# ESP32.net
KiCad netlist of a schematic drawn in Altium Designer
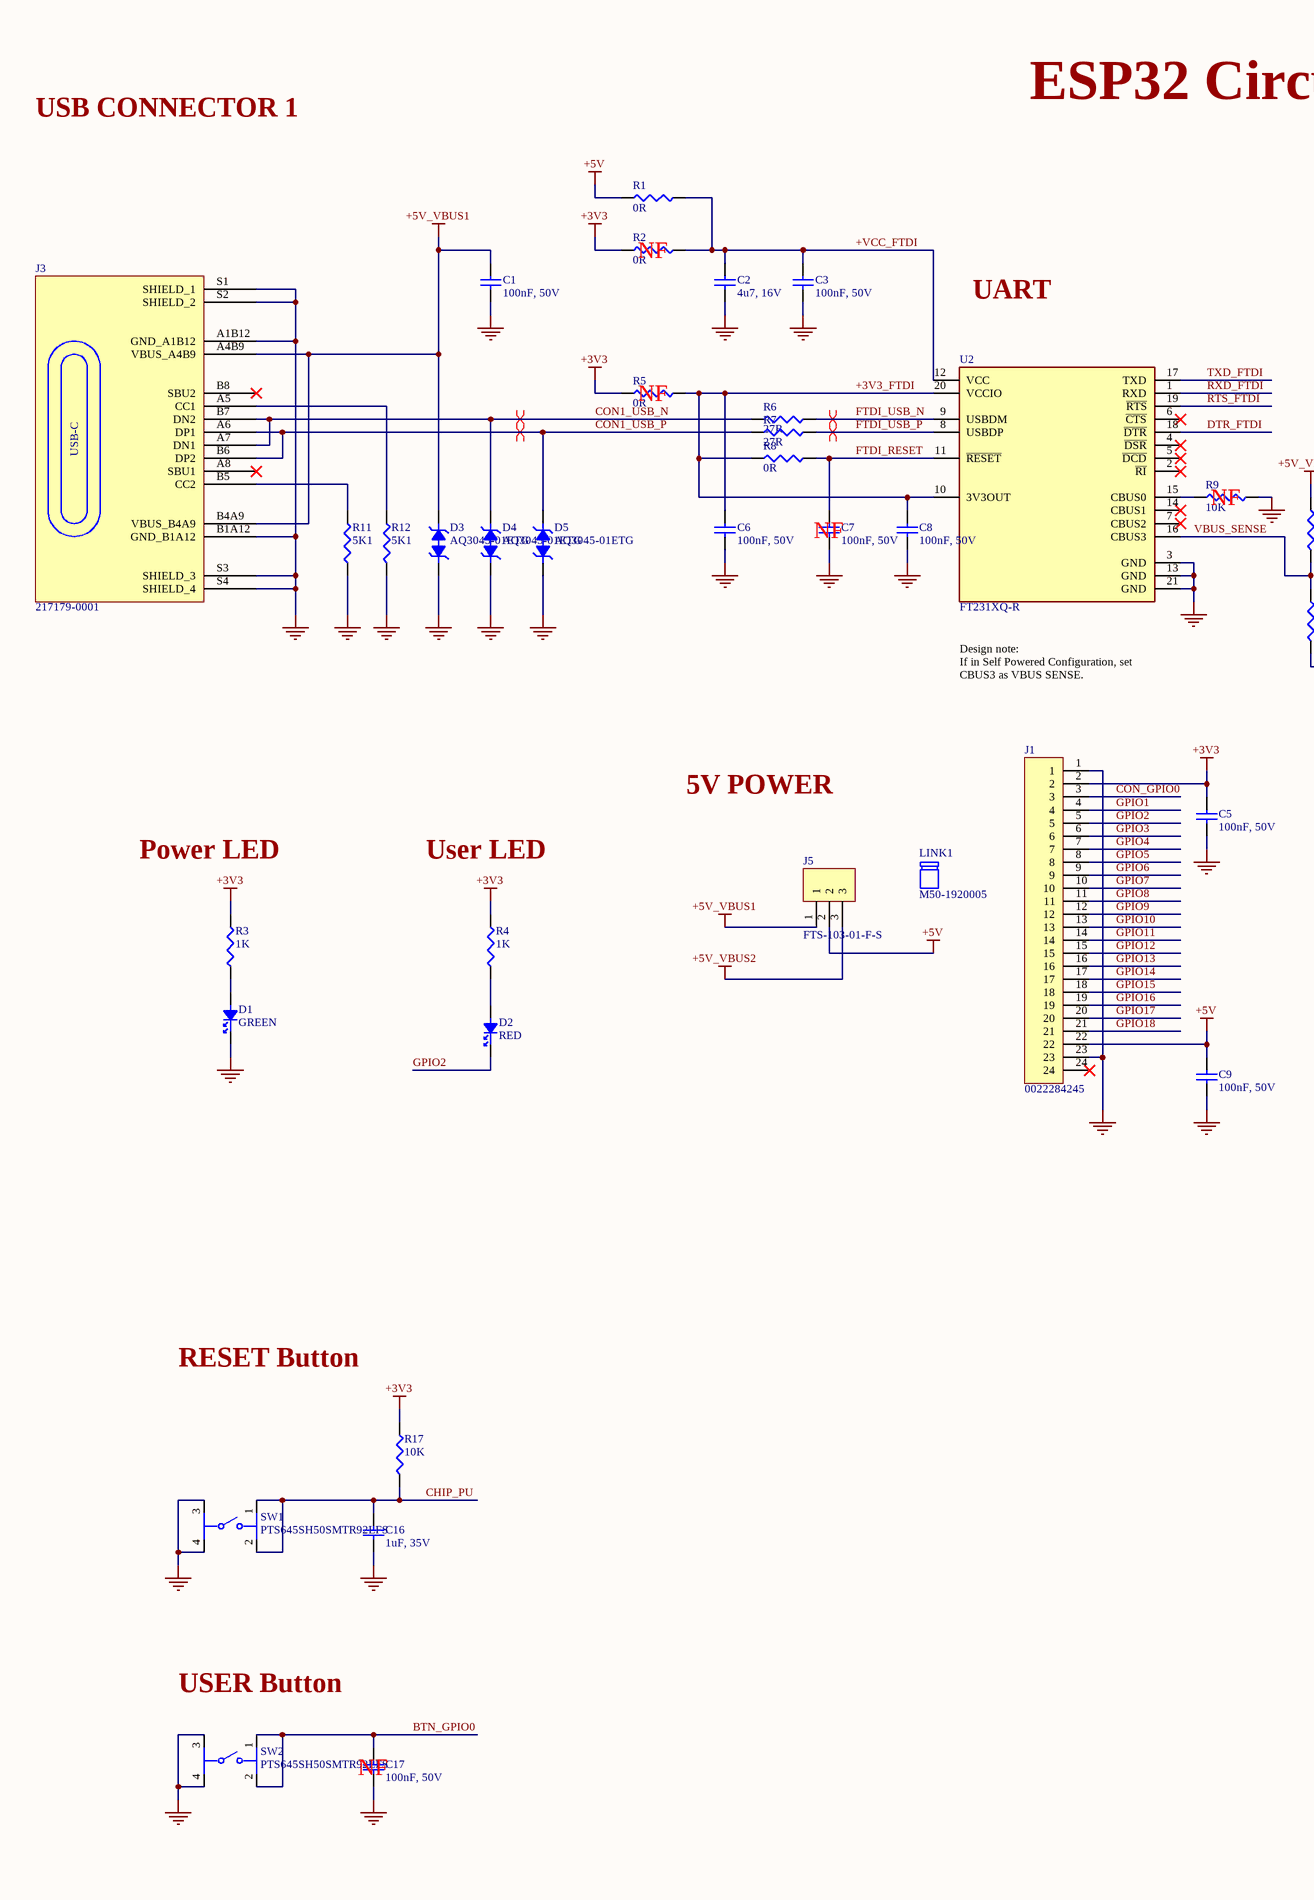
[diagram p0: ESP32 .SchDoc, left]
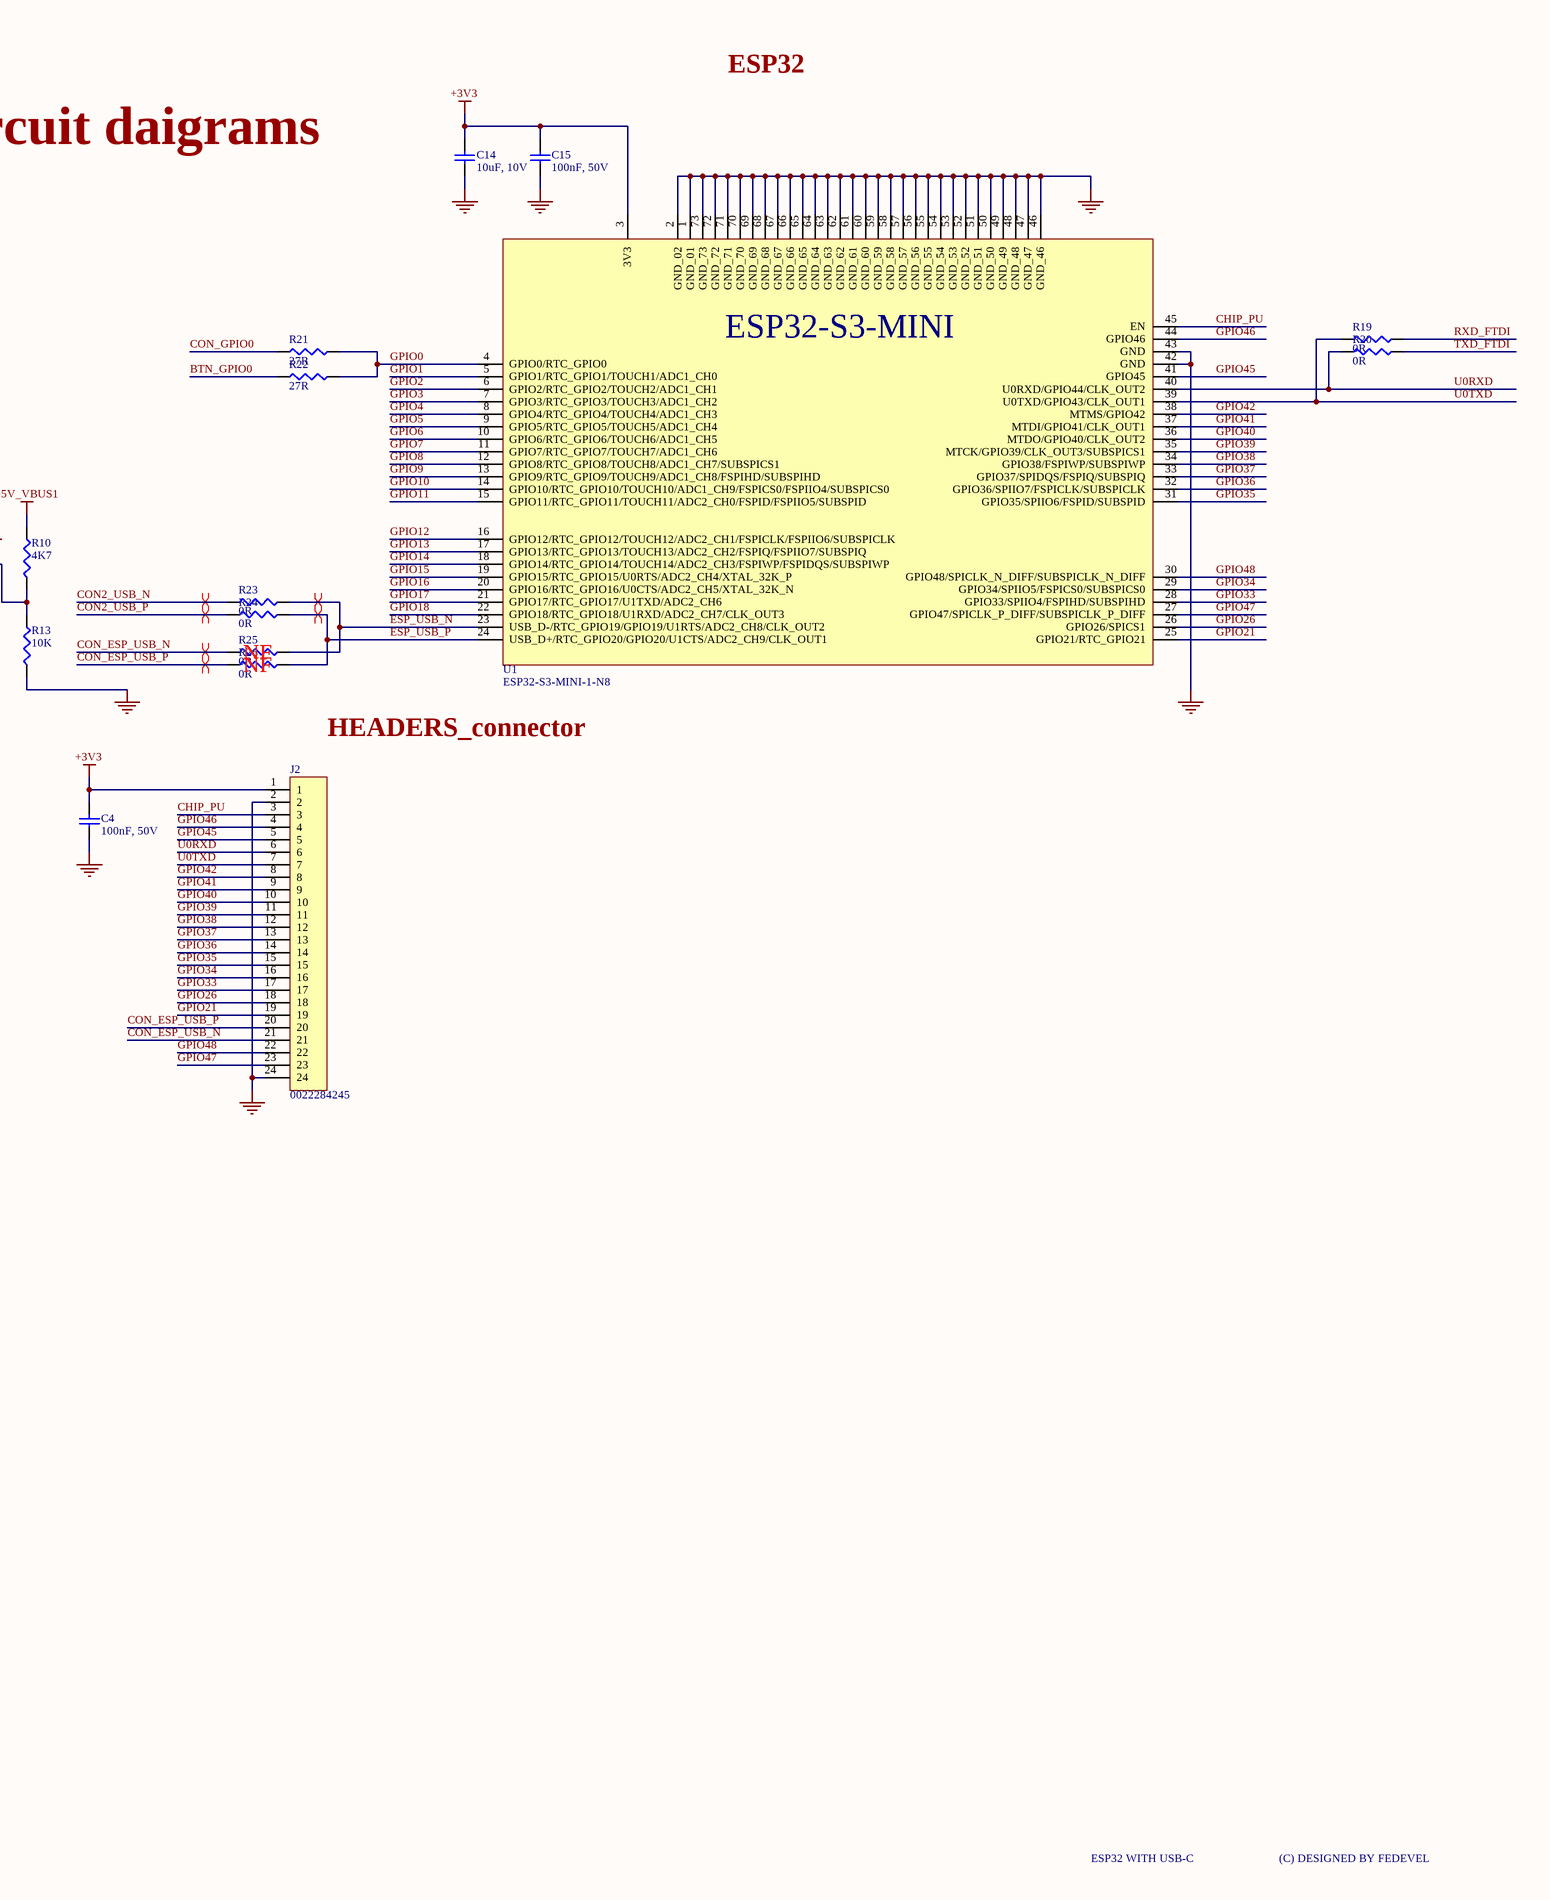
[diagram p1: ESP32 .SchDoc, right]

(export (version "E")
  (design (tool "Eeschema 10.0.6"))
  (components
    (comp (ref "C1")
      (value "100nF, 50V")
      (footprint "CAPC1005X55N")
      (description "CAP CER 0.1UF 50V X7R 0402")
      (fields
        (field (name "MANUFACTURER") "Samsung")
        (field (name "MANUFACTURER PART NUMBER") "CL05B104KB54PNC")
      )
      (libsource (lib "Schlib") (part "CL05B104KB54PNC"))
    )
    (comp (ref "C2")
      (value "4u7, 16V")
      (footprint "CAPC1005X55N")
      (description "CAP CER 4.7UF 16V X5R 0402")
      (fields
        (field (name "MANUFACTURER") "Samsung")
        (field (name "MANUFACTURER PART NUMBER") "CL05A475MO5NUNC")
      )
      (libsource (lib "Schlib") (part "CL05A475MO5NUNC"))
    )
    (comp (ref "C3")
      (value "100nF, 50V")
      (footprint "CAPC1005X55N")
      (description "CAP CER 0.1UF 50V X7R 0402")
      (fields
        (field (name "MANUFACTURER") "Samsung")
        (field (name "MANUFACTURER PART NUMBER") "CL05B104KB54PNC")
      )
      (libsource (lib "Schlib") (part "CL05B104KB54PNC"))
    )
    (comp (ref "C4")
      (value "100nF, 50V")
      (footprint "CAPC1005X55N")
      (description "CAP CER 0.1UF 50V X7R 0402")
      (fields
        (field (name "MANUFACTURER") "Samsung")
        (field (name "MANUFACTURER PART NUMBER") "CL05B104KB54PNC")
      )
      (libsource (lib "Schlib") (part "CL05B104KB54PNC"))
    )
    (comp (ref "C5")
      (value "100nF, 50V")
      (footprint "CAPC1005X55N")
      (description "CAP CER 0.1UF 50V X7R 0402")
      (fields
        (field (name "MANUFACTURER") "Samsung")
        (field (name "MANUFACTURER PART NUMBER") "CL05B104KB54PNC")
      )
      (libsource (lib "Schlib") (part "CL05B104KB54PNC"))
    )
    (comp (ref "C6")
      (value "100nF, 50V")
      (footprint "CAPC1005X55N")
      (description "CAP CER 0.1UF 50V X7R 0402")
      (fields
        (field (name "MANUFACTURER") "Samsung")
        (field (name "MANUFACTURER PART NUMBER") "CL05B104KB54PNC")
      )
      (libsource (lib "Schlib") (part "CL05B104KB54PNC"))
    )
    (comp (ref "C7")
      (value "100nF, 50V")
      (footprint "CAPC1005X55N")
      (description "CAP CER 0.1UF 50V X7R 0402")
      (fields
        (field (name "MANUFACTURER") "Samsung")
        (field (name "MANUFACTURER PART NUMBER") "CL05B104KB54PNC")
      )
      (libsource (lib "Schlib") (part "CL05B104KB54PNC"))
    )
    (comp (ref "C8")
      (value "100nF, 50V")
      (footprint "CAPC1005X55N")
      (description "CAP CER 0.1UF 50V X7R 0402")
      (fields
        (field (name "MANUFACTURER") "Samsung")
        (field (name "MANUFACTURER PART NUMBER") "CL05B104KB54PNC")
      )
      (libsource (lib "Schlib") (part "CL05B104KB54PNC"))
    )
    (comp (ref "C9")
      (value "100nF, 50V")
      (footprint "CAPC1005X55N")
      (description "CAP CER 0.1UF 50V X7R 0402")
      (fields
        (field (name "MANUFACTURER") "Samsung")
        (field (name "MANUFACTURER PART NUMBER") "CL05B104KB54PNC")
      )
      (libsource (lib "Schlib") (part "CL05B104KB54PNC"))
    )
    (comp (ref "C14")
      (value "10uF, 10V")
      (footprint "CAPC1005X55N")
      (description "CAP CER 10UF 10V X5R 0402")
      (fields
        (field (name "MANUFACTURER") "Samsung")
        (field (name "MANUFACTURER PART NUMBER") "CL05A106MP8NUB8")
      )
      (libsource (lib "Schlib") (part "CL05A106MP8NUB8"))
    )
    (comp (ref "C15")
      (value "100nF, 50V")
      (footprint "CAPC1005X55N")
      (description "CAP CER 0.1UF 50V X7R 0402")
      (fields
        (field (name "MANUFACTURER") "Samsung")
        (field (name "MANUFACTURER PART NUMBER") "CL05B104KB54PNC")
      )
      (libsource (lib "Schlib") (part "CL05B104KB54PNC"))
    )
    (comp (ref "C16")
      (value "1uF, 35V")
      (footprint "CAPC1005X55N")
      (description "CAP CER 1UF 35V X5R 0402")
      (fields
        (field (name "MANUFACTURER") "Samsung")
        (field (name "MANUFACTURER PART NUMBER") "CL05A105KL5NRNC")
      )
      (libsource (lib "Schlib") (part "CL05A105KL5NRNC"))
    )
    (comp (ref "C17")
      (value "100nF, 50V")
      (footprint "CAPC1005X55N")
      (description "CAP CER 0.1UF 50V X7R 0402")
      (fields
        (field (name "MANUFACTURER") "Samsung")
        (field (name "MANUFACTURER PART NUMBER") "CL05B104KB54PNC")
      )
      (libsource (lib "Schlib") (part "CL05B104KB54PNC"))
    )
    (comp (ref "D1")
      (value "GREEN")
      (footprint "LED0402G")
      (description "LED YLW-GRN 0402 SMD")
      (fields
        (field (name "MANUFACTURER") "Vishay")
        (field (name "MANUFACTURER PART NUMBER") "VLMG1500-GS08")
      )
      (libsource (lib "Schlib") (part "VLMG1500-GS08"))
    )
    (comp (ref "D2")
      (value "RED")
      (footprint "LED0402R")
      (description "LED RED 0402 SMD")
      (fields
        (field (name "MANUFACTURER") "Vishay")
        (field (name "MANUFACTURER PART NUMBER") "VLMS1500-GS08")
      )
      (libsource (lib "Schlib") (part "VLMS1500-GS08"))
    )
    (comp (ref "D3")
      (value "AQ3045-01ETG")
      (footprint "SOD882")
      (description "TVS DIODE 5.3VWM 12VC SOD882")
      (fields (field (name "MANUFACTURER") "Littelfuse") (field (name "LCSC PART NUMBER") "C3710326"))
      (libsource (lib "Schlib") (part "AQ3045-01ETG"))
    )
    (comp (ref "D4")
      (value "AQ3045-01ETG")
      (footprint "SOD882")
      (description "TVS DIODE 5.3VWM 12VC SOD882")
      (fields (field (name "MANUFACTURER") "Littelfuse") (field (name "LCSC PART NUMBER") "C3710326"))
      (libsource (lib "Schlib") (part "AQ3045-01ETG"))
    )
    (comp (ref "D5")
      (value "AQ3045-01ETG")
      (footprint "SOD882")
      (description "TVS DIODE 5.3VWM 12VC SOD882")
      (fields (field (name "MANUFACTURER") "Littelfuse") (field (name "LCSC PART NUMBER") "C3710326"))
      (libsource (lib "Schlib") (part "AQ3045-01ETG"))
    )
    (comp (ref "J1")
      (value "0022284245")
      (footprint "HDR_1X24_2.54MM")
      (description "CONN HEADER VERT 24POS 2.54MM")
      (fields (field (name "MANUFACTURER") "Molex") (field (name "LCSC PART NUMBER") "C7145888"))
      (libsource (lib "Schlib") (part "0022284245"))
    )
    (comp (ref "J2")
      (value "0022284245")
      (footprint "HDR_1X24_2.54MM")
      (description "CONN HEADER VERT 24POS 2.54MM")
      (fields (field (name "MANUFACTURER") "Molex") (field (name "LCSC PART NUMBER") "C7145888"))
      (libsource (lib "") (part "0022284245_1"))
    )
    (comp (ref "J3")
      (value "217179-0001")
      (footprint "FP-2171790001-MFG")
      (description "CONN RCP USB2.0 TYP C 24P SMD RA")
      (fields (field (name "MANUFACTURER") "Molex") (field (name "LCSC PART NUMBER") "C3197684"))
      (libsource (lib "Schlib") (part "217179-0001"))
    )
    (comp (ref "J5")
      (value "FTS-103-01-F-S")
      (footprint "HDR_1X3_1.27MM")
      (description "CONN HEADER VERT 3POS 1.27MM")
      (fields (field (name "MANUFACTURER") "Samtec") (field (name "LCSC PART NUMBER") "C3333578"))
      (libsource (lib "Schlib") (part "FTS-103-01-F-S"))
    )
    (comp (ref "LINK1")
      (value "M50-1920005")
      (description "CONN SHUNT 1.27MM RED")
      (fields (field (name "MANUFACTURER") "Harwin") (field (name "LCSC PART NUMBER") "C6985646"))
      (libsource (lib "Schlib") (part "M50-1920005"))
    )
    (comp (ref "R1")
      (value "0R")
      (footprint "RESC1005X37N")
      (description "RES 0 OHM JUMPER 1/16W 0402")
      (fields
        (field (name "MANUFACTURER") "Yageo")
        (field (name "MANUFACTURER PART NUMBER") "RC0402JR-070RL")
      )
      (libsource (lib "Schlib") (part "RC0402JR-070RL"))
    )
    (comp (ref "R2")
      (value "0R")
      (footprint "RESC1005X37N")
      (description "RES 0 OHM JUMPER 1/16W 0402")
      (fields
        (field (name "MANUFACTURER") "Yageo")
        (field (name "MANUFACTURER PART NUMBER") "RC0402JR-070RL")
      )
      (libsource (lib "Schlib") (part "RC0402JR-070RL"))
    )
    (comp (ref "R3")
      (value "1K")
      (footprint "RESC1005X37N")
      (description "RES 1K OHM 1% 1/16W 0402")
      (fields
        (field (name "MANUFACTURER") "Yageo")
        (field (name "MANUFACTURER PART NUMBER") "RC0402FR-071KL")
      )
      (libsource (lib "Schlib") (part "RC0402FR-071KL"))
    )
    (comp (ref "R4")
      (value "1K")
      (footprint "RESC1005X37N")
      (description "RES 1K OHM 1% 1/16W 0402")
      (fields
        (field (name "MANUFACTURER") "Yageo")
        (field (name "MANUFACTURER PART NUMBER") "RC0402FR-071KL")
      )
      (libsource (lib "Schlib") (part "RC0402FR-071KL"))
    )
    (comp (ref "R5")
      (value "0R")
      (footprint "RESC1005X37N")
      (description "RES 0 OHM JUMPER 1/16W 0402")
      (fields
        (field (name "MANUFACTURER") "Yageo")
        (field (name "MANUFACTURER PART NUMBER") "RC0402JR-070RL")
      )
      (libsource (lib "Schlib") (part "RC0402JR-070RL"))
    )
    (comp (ref "R6")
      (value "27R")
      (footprint "RESC1005X37N")
      (description "RES 27 OHM 1% 1/16W 0402")
      (fields
        (field (name "MANUFACTURER") "Yageo")
        (field (name "MANUFACTURER PART NUMBER") "RC0402FR-0727RL")
      )
      (libsource (lib "Schlib") (part "RC0402FR-0727RL"))
    )
    (comp (ref "R7")
      (value "27R")
      (footprint "RESC1005X37N")
      (description "RES 27 OHM 1% 1/16W 0402")
      (fields
        (field (name "MANUFACTURER") "Yageo")
        (field (name "MANUFACTURER PART NUMBER") "RC0402FR-0727RL")
      )
      (libsource (lib "Schlib") (part "RC0402FR-0727RL"))
    )
    (comp (ref "R8")
      (value "0R")
      (footprint "RESC1005X37N")
      (description "RES 0 OHM JUMPER 1/16W 0402")
      (fields
        (field (name "MANUFACTURER") "Yageo")
        (field (name "MANUFACTURER PART NUMBER") "RC0402JR-070RL")
      )
      (libsource (lib "Schlib") (part "RC0402JR-070RL"))
    )
    (comp (ref "R9")
      (value "10K")
      (footprint "RESC1005X37N")
      (description "RES SMD 10K OHM 1% 1/16W 0402")
      (fields
        (field (name "MANUFACTURER") "Yageo")
        (field (name "MANUFACTURER PART NUMBER") "AC0402FR-0710KL")
      )
      (libsource (lib "Schlib") (part "AC0402FR-0710KL"))
    )
    (comp (ref "R10")
      (value "4K7")
      (footprint "RESC1005X37N")
      (description "RES 4.7K OHM 1% 1/16W 0402")
      (fields
        (field (name "MANUFACTURER") "Yageo")
        (field (name "MANUFACTURER PART NUMBER") "RC0402FR-074K7L")
      )
      (libsource (lib "Schlib") (part "RC0402FR-074K7L"))
    )
    (comp (ref "R11")
      (value "5K1")
      (footprint "RESC1005X37N")
      (description "RES SMD 5.1K OHM 1% 1/16W 0402")
      (fields
        (field (name "MANUFACTURER") "Yageo")
        (field (name "MANUFACTURER PART NUMBER") "AC0402FR-075K1L")
      )
      (libsource (lib "Schlib") (part "AC0402FR-075K1L"))
    )
    (comp (ref "R12")
      (value "5K1")
      (footprint "RESC1005X37N")
      (description "RES SMD 5.1K OHM 1% 1/16W 0402")
      (fields
        (field (name "MANUFACTURER") "Yageo")
        (field (name "MANUFACTURER PART NUMBER") "AC0402FR-075K1L")
      )
      (libsource (lib "Schlib") (part "AC0402FR-075K1L"))
    )
    (comp (ref "R13")
      (value "10K")
      (footprint "RESC1005X37N")
      (description "RES SMD 10K OHM 1% 1/16W 0402")
      (fields
        (field (name "MANUFACTURER") "Yageo")
        (field (name "MANUFACTURER PART NUMBER") "AC0402FR-0710KL")
      )
      (libsource (lib "Schlib") (part "AC0402FR-0710KL"))
    )
    (comp (ref "R17")
      (value "10K")
      (footprint "RESC1005X37N")
      (description "RES SMD 10K OHM 1% 1/16W 0402")
      (fields
        (field (name "MANUFACTURER") "Yageo")
        (field (name "MANUFACTURER PART NUMBER") "AC0402FR-0710KL")
      )
      (libsource (lib "Schlib") (part "AC0402FR-0710KL"))
    )
    (comp (ref "R19")
      (value "0R")
      (footprint "RESC1005X37N")
      (description "RES 0 OHM JUMPER 1/16W 0402")
      (fields
        (field (name "MANUFACTURER") "Yageo")
        (field (name "MANUFACTURER PART NUMBER") "RC0402JR-070RL")
      )
      (libsource (lib "Schlib") (part "RC0402JR-070RL"))
    )
    (comp (ref "R20")
      (value "0R")
      (footprint "RESC1005X37N")
      (description "RES 0 OHM JUMPER 1/16W 0402")
      (fields
        (field (name "MANUFACTURER") "Yageo")
        (field (name "MANUFACTURER PART NUMBER") "RC0402JR-070RL")
      )
      (libsource (lib "Schlib") (part "RC0402JR-070RL"))
    )
    (comp (ref "R21")
      (value "27R")
      (footprint "RESC1005X37N")
      (description "RES 27 OHM 1% 1/16W 0402")
      (fields
        (field (name "MANUFACTURER") "Yageo")
        (field (name "MANUFACTURER PART NUMBER") "RC0402FR-0727RL")
      )
      (libsource (lib "Schlib") (part "RC0402FR-0727RL"))
    )
    (comp (ref "R22")
      (value "27R")
      (footprint "RESC1005X37N")
      (description "RES 27 OHM 1% 1/16W 0402")
      (fields
        (field (name "MANUFACTURER") "Yageo")
        (field (name "MANUFACTURER PART NUMBER") "RC0402FR-0727RL")
      )
      (libsource (lib "Schlib") (part "RC0402FR-0727RL"))
    )
    (comp (ref "R23")
      (value "0R")
      (footprint "RESC1005X37N")
      (description "RES 0 OHM JUMPER 1/16W 0402")
      (fields
        (field (name "MANUFACTURER") "Yageo")
        (field (name "MANUFACTURER PART NUMBER") "RC0402JR-070RL")
      )
      (libsource (lib "Schlib") (part "RC0402JR-070RL"))
    )
    (comp (ref "R24")
      (value "0R")
      (footprint "RESC1005X37N")
      (description "RES 0 OHM JUMPER 1/16W 0402")
      (fields
        (field (name "MANUFACTURER") "Yageo")
        (field (name "MANUFACTURER PART NUMBER") "RC0402JR-070RL")
      )
      (libsource (lib "Schlib") (part "RC0402JR-070RL"))
    )
    (comp (ref "R25")
      (value "0R")
      (footprint "RESC1005X37N")
      (description "RES 0 OHM JUMPER 1/16W 0402")
      (fields
        (field (name "MANUFACTURER") "Yageo")
        (field (name "MANUFACTURER PART NUMBER") "RC0402JR-070RL")
      )
      (libsource (lib "Schlib") (part "RC0402JR-070RL"))
    )
    (comp (ref "R26")
      (value "0R")
      (footprint "RESC1005X37N")
      (description "RES 0 OHM JUMPER 1/16W 0402")
      (fields
        (field (name "MANUFACTURER") "Yageo")
        (field (name "MANUFACTURER PART NUMBER") "RC0402JR-070RL")
      )
      (libsource (lib "Schlib") (part "RC0402JR-070RL"))
    )
    (comp (ref "SW1")
      (value "PTS645SH50SMTR92LFS")
      (footprint "FP-PTS645SH50SMTR92LFS-MFG")
      (description "SWITCH TACTILE SPST-NO 0.05A 12V")
      (fields (field (name "MANUFACTURER") "ITT C&K") (field (name "LCSC PART NUMBER") "C221869"))
      (libsource (lib "Schlib") (part "PTS645SH50SMTR92LFS"))
    )
    (comp (ref "SW2")
      (value "PTS645SH50SMTR92LFS")
      (footprint "FP-PTS645SH50SMTR92LFS-MFG")
      (description "SWITCH TACTILE SPST-NO 0.05A 12V")
      (fields (field (name "MANUFACTURER") "ITT C&K") (field (name "LCSC PART NUMBER") "C221869"))
      (libsource (lib "Schlib") (part "PTS645SH50SMTR92LFS"))
    )
    (comp (ref "U1")
      (value "ESP32-S3-MINI-1-N8")
      (footprint "XCVR_ESP32-S3-MINI-1-N8")
      (description "SMD Module, ESP32-S3FN8, 8 mb Sp")
      (fields (field (name "MANUFACTURER") "Espressif Systems") (field (name "LCSC PART NUMBER") "C2913206"))
      (libsource (lib "Schlib") (part "ESP32-S3-MINI-1-N8"))
    )
    (comp (ref "U2")
      (value "FT231XQ-R")
      (footprint "FP-QFN-20-IPC_B")
      (description "IC USB SERIAL FULL UART 20QFN")
      (fields (field (name "MANUFACTURER") "FTDI") (field (name "LCSC PART NUMBER") "C132159"))
      (libsource (lib "Schlib") (part "FT231XQ-R"))
    )
  )
  (nets
    (net (code "1") (name "+3V3") (class "Default")
      (node (ref "C14") (pin "2") (pinfunction "2_2") (pintype "passive"))
      (node (ref "C15") (pin "2") (pinfunction "2_2") (pintype "passive"))
      (node (ref "C4") (pin "2") (pinfunction "2_2") (pintype "passive"))
      (node (ref "C5") (pin "2") (pinfunction "2_2") (pintype "passive"))
      (node (ref "J1") (pin "2") (pinfunction "2_2") (pintype "passive"))
      (node (ref "J2") (pin "1") (pinfunction "1_1") (pintype "passive"))
      (node (ref "R17") (pin "2") (pinfunction "2_2") (pintype "passive"))
      (node (ref "R2") (pin "1") (pinfunction "1_1") (pintype "passive"))
      (node (ref "R3") (pin "2") (pinfunction "2_2") (pintype "passive"))
      (node (ref "R4") (pin "2") (pinfunction "2_2") (pintype "passive"))
      (node (ref "R5") (pin "1") (pinfunction "1_1") (pintype "passive"))
      (node (ref "U1") (pin "3") (pinfunction "3V3_3") (pintype "passive"))
    )
    (net (code "2") (name "+5V") (class "Default")
      (node (ref "C9") (pin "2") (pinfunction "2_2") (pintype "passive"))
      (node (ref "J1") (pin "22") (pinfunction "22_22") (pintype "passive"))
      (node (ref "J5") (pin "2") (pinfunction "2_2") (pintype "passive"))
      (node (ref "R1") (pin "1") (pinfunction "1_1") (pintype "passive"))
    )
    (net (code "3") (name "+5V_VBUS1") (class "Default")
      (node (ref "C1") (pin "2") (pinfunction "2_2") (pintype "passive"))
      (node (ref "D3") (pin "2") (pinfunction "2_2") (pintype "passive"))
      (node (ref "J3") (pin "A4B9") (pinfunction "VBUS_A4B9_A4B9") (pintype "passive"))
      (node (ref "J3") (pin "B4A9") (pinfunction "VBUS_B4A9_B4A9") (pintype "passive"))
      (node (ref "J5") (pin "1") (pinfunction "1_1") (pintype "passive"))
      (node (ref "R10") (pin "2") (pinfunction "2_2") (pintype "passive"))
    )
    (net (code "4") (name "+5V_VBUS2") (class "Default")
      (node (ref "J5") (pin "3") (pinfunction "3_3") (pintype "passive"))
    )
    (net (code "5") (name "/+3V3_FTDI") (class "Default")
      (node (ref "C6") (pin "2") (pinfunction "2_2") (pintype "passive"))
      (node (ref "C8") (pin "2") (pinfunction "2_2") (pintype "passive"))
      (node (ref "R5") (pin "2") (pinfunction "2_2") (pintype "passive"))
      (node (ref "R8") (pin "1") (pinfunction "1_1") (pintype "passive"))
      (node (ref "U2") (pin "10") (pinfunction "3V3OUT_10") (pintype "passive"))
      (node (ref "U2") (pin "20") (pinfunction "VCCIO_20") (pintype "passive"))
    )
    (net (code "6") (name "/+VCC_FTDI") (class "Default")
      (node (ref "C2") (pin "2") (pinfunction "2_2") (pintype "passive"))
      (node (ref "C3") (pin "2") (pinfunction "2_2") (pintype "passive"))
      (node (ref "R1") (pin "2") (pinfunction "2_2") (pintype "passive"))
      (node (ref "R2") (pin "2") (pinfunction "2_2") (pintype "passive"))
      (node (ref "U2") (pin "12") (pinfunction "VCC_12") (pintype "passive"))
    )
    (net (code "7") (name "/BTN_GPIO0") (class "Default")
      (node (ref "C17") (pin "2") (pinfunction "2_2") (pintype "passive"))
      (node (ref "R22") (pin "1") (pinfunction "1_1") (pintype "passive"))
      (node (ref "SW2") (pin "1") (pinfunction "1_1") (pintype "passive"))
      (node (ref "SW2") (pin "2") (pinfunction "2_2") (pintype "passive"))
    )
    (net (code "8") (name "/CHIP_PU") (class "Default")
      (node (ref "C16") (pin "2") (pinfunction "2_2") (pintype "passive"))
      (node (ref "J2") (pin "3") (pinfunction "3_3") (pintype "passive"))
      (node (ref "R17") (pin "1") (pinfunction "1_1") (pintype "passive"))
      (node (ref "SW1") (pin "1") (pinfunction "1_1") (pintype "passive"))
      (node (ref "SW1") (pin "2") (pinfunction "2_2") (pintype "passive"))
      (node (ref "U1") (pin "45") (pinfunction "EN_45") (pintype "passive"))
    )
    (net (code "9") (name "/CON1_USB_N") (class "Default")
      (node (ref "D4") (pin "2") (pinfunction "2_2") (pintype "passive"))
      (node (ref "J3") (pin "A7") (pinfunction "DN1_A7") (pintype "passive"))
      (node (ref "J3") (pin "B7") (pinfunction "DN2_B7") (pintype "passive"))
      (node (ref "R6") (pin "1") (pinfunction "1_1") (pintype "passive"))
    )
    (net (code "10") (name "/CON1_USB_P") (class "Default")
      (node (ref "D5") (pin "2") (pinfunction "2_2") (pintype "passive"))
      (node (ref "J3") (pin "A6") (pinfunction "DP1_A6") (pintype "passive"))
      (node (ref "J3") (pin "B6") (pinfunction "DP2_B6") (pintype "passive"))
      (node (ref "R7") (pin "1") (pinfunction "1_1") (pintype "passive"))
    )
    (net (code "11") (name "/CON2_USB_N") (class "Default")
      (node (ref "R23") (pin "1") (pinfunction "1_1") (pintype "passive"))
    )
    (net (code "12") (name "/CON2_USB_P") (class "Default")
      (node (ref "R24") (pin "1") (pinfunction "1_1") (pintype "passive"))
    )
    (net (code "13") (name "/CON_ESP_USB_N") (class "Default")
      (node (ref "J2") (pin "21") (pinfunction "21_21") (pintype "passive"))
      (node (ref "R25") (pin "1") (pinfunction "1_1") (pintype "passive"))
    )
    (net (code "14") (name "/CON_ESP_USB_P") (class "Default")
      (node (ref "J2") (pin "20") (pinfunction "20_20") (pintype "passive"))
      (node (ref "R26") (pin "1") (pinfunction "1_1") (pintype "passive"))
    )
    (net (code "15") (name "/CON_GPIO0") (class "Default")
      (node (ref "J1") (pin "3") (pinfunction "3_3") (pintype "passive"))
      (node (ref "R21") (pin "1") (pinfunction "1_1") (pintype "passive"))
    )
    (net (code "16") (name "/DTR_FTDI") (class "Default")
      (node (ref "U2") (pin "18") (pinfunction "~{DTR}_18") (pintype "passive"))
    )
    (net (code "17") (name "/ESP_USB_N") (class "Default")
      (node (ref "R23") (pin "2") (pinfunction "2_2") (pintype "passive"))
      (node (ref "R25") (pin "2") (pinfunction "2_2") (pintype "passive"))
      (node (ref "U1") (pin "23") (pinfunction "USB_D-/RTC_GPIO19/GPIO19/U1RTS/ADC2_CH8/CLK_OUT2_23") (pintype "passive"))
    )
    (net (code "18") (name "/ESP_USB_P") (class "Default")
      (node (ref "R24") (pin "2") (pinfunction "2_2") (pintype "passive"))
      (node (ref "R26") (pin "2") (pinfunction "2_2") (pintype "passive"))
      (node (ref "U1") (pin "24") (pinfunction "USB_D+/RTC_GPIO20/GPIO20/U1CTS/ADC2_CH9/CLK_OUT1_24") (pintype "passive"))
    )
    (net (code "19") (name "/FTDI_RESET") (class "Default")
      (node (ref "C7") (pin "2") (pinfunction "2_2") (pintype "passive"))
      (node (ref "R8") (pin "2") (pinfunction "2_2") (pintype "passive"))
      (node (ref "U2") (pin "11") (pinfunction "~{RESET}_11") (pintype "passive"))
    )
    (net (code "20") (name "/FTDI_USB_N") (class "Default")
      (node (ref "R6") (pin "2") (pinfunction "2_2") (pintype "passive"))
      (node (ref "U2") (pin "9") (pinfunction "USBDM_9") (pintype "passive"))
    )
    (net (code "21") (name "/FTDI_USB_P") (class "Default")
      (node (ref "R7") (pin "2") (pinfunction "2_2") (pintype "passive"))
      (node (ref "U2") (pin "8") (pinfunction "USBDP_8") (pintype "passive"))
    )
    (net (code "22") (name "/GPIO0") (class "Default")
      (node (ref "R21") (pin "2") (pinfunction "2_2") (pintype "passive"))
      (node (ref "R22") (pin "2") (pinfunction "2_2") (pintype "passive"))
      (node (ref "U1") (pin "4") (pinfunction "GPIO0/RTC_GPIO0_4") (pintype "passive"))
    )
    (net (code "23") (name "/GPIO1") (class "Default")
      (node (ref "J1") (pin "4") (pinfunction "4_4") (pintype "passive"))
      (node (ref "U1") (pin "5") (pinfunction "GPIO1/RTC_GPIO1/TOUCH1/ADC1_CH0_5") (pintype "passive"))
    )
    (net (code "24") (name "/GPIO2") (class "Default")
      (node (ref "D2") (pin "1") (pinfunction "1_1") (pintype "passive"))
      (node (ref "J1") (pin "5") (pinfunction "5_5") (pintype "passive"))
      (node (ref "U1") (pin "6") (pinfunction "GPIO2/RTC_GPIO2/TOUCH2/ADC1_CH1_6") (pintype "passive"))
    )
    (net (code "25") (name "/GPIO3") (class "Default")
      (node (ref "J1") (pin "6") (pinfunction "6_6") (pintype "passive"))
      (node (ref "U1") (pin "7") (pinfunction "GPIO3/RTC_GPIO3/TOUCH3/ADC1_CH2_7") (pintype "passive"))
    )
    (net (code "26") (name "/GPIO4") (class "Default")
      (node (ref "J1") (pin "7") (pinfunction "7_7") (pintype "passive"))
      (node (ref "U1") (pin "8") (pinfunction "GPIO4/RTC_GPIO4/TOUCH4/ADC1_CH3_8") (pintype "passive"))
    )
    (net (code "27") (name "/GPIO5") (class "Default")
      (node (ref "J1") (pin "8") (pinfunction "8_8") (pintype "passive"))
      (node (ref "U1") (pin "9") (pinfunction "GPIO5/RTC_GPIO5/TOUCH5/ADC1_CH4_9") (pintype "passive"))
    )
    (net (code "28") (name "/GPIO6") (class "Default")
      (node (ref "J1") (pin "9") (pinfunction "9_9") (pintype "passive"))
      (node (ref "U1") (pin "10") (pinfunction "GPIO6/RTC_GPIO6/TOUCH6/ADC1_CH5_10") (pintype "passive"))
    )
    (net (code "29") (name "/GPIO7") (class "Default")
      (node (ref "J1") (pin "10") (pinfunction "10_10") (pintype "passive"))
      (node (ref "U1") (pin "11") (pinfunction "GPIO7/RTC_GPIO7/TOUCH7/ADC1_CH6_11") (pintype "passive"))
    )
    (net (code "30") (name "/GPIO8") (class "Default")
      (node (ref "J1") (pin "11") (pinfunction "11_11") (pintype "passive"))
      (node (ref "U1") (pin "12") (pinfunction "GPIO8/RTC_GPIO8/TOUCH8/ADC1_CH7/SUBSPICS1_12") (pintype "passive"))
    )
    (net (code "31") (name "/GPIO9") (class "Default")
      (node (ref "J1") (pin "12") (pinfunction "12_12") (pintype "passive"))
      (node (ref "U1") (pin "13") (pinfunction "GPIO9/RTC_GPIO9/TOUCH9/ADC1_CH8/FSPIHD/SUBSPIHD_13") (pintype "passive"))
    )
    (net (code "32") (name "/GPIO10") (class "Default")
      (node (ref "J1") (pin "13") (pinfunction "13_13") (pintype "passive"))
      (node (ref "U1") (pin "14") (pinfunction "GPIO10/RTC_GPIO10/TOUCH10/ADC1_CH9/FSPICS0/FSPIIO4/SUBSPICS0_14") (pintype "passive"))
    )
    (net (code "33") (name "/GPIO11") (class "Default")
      (node (ref "J1") (pin "14") (pinfunction "14_14") (pintype "passive"))
      (node (ref "U1") (pin "15") (pinfunction "GPIO11/RTC_GPIO11/TOUCH11/ADC2_CH0/FSPID/FSPIIO5/SUBSPID_15") (pintype "passive"))
    )
    (net (code "34") (name "/GPIO12") (class "Default")
      (node (ref "J1") (pin "15") (pinfunction "15_15") (pintype "passive"))
      (node (ref "U1") (pin "16") (pinfunction "GPIO12/RTC_GPIO12/TOUCH12/ADC2_CH1/FSPICLK/FSPIIO6/SUBSPICLK_16") (pintype "passive"))
    )
    (net (code "35") (name "/GPIO13") (class "Default")
      (node (ref "J1") (pin "16") (pinfunction "16_16") (pintype "passive"))
      (node (ref "U1") (pin "17") (pinfunction "GPIO13/RTC_GPIO13/TOUCH13/ADC2_CH2/FSPIQ/FSPIIO7/SUBSPIQ_17") (pintype "passive"))
    )
    (net (code "36") (name "/GPIO14") (class "Default")
      (node (ref "J1") (pin "17") (pinfunction "17_17") (pintype "passive"))
      (node (ref "U1") (pin "18") (pinfunction "GPIO14/RTC_GPIO14/TOUCH14/ADC2_CH3/FSPIWP/FSPIDQS/SUBSPIWP_18") (pintype "passive"))
    )
    (net (code "37") (name "/GPIO15") (class "Default")
      (node (ref "J1") (pin "18") (pinfunction "18_18") (pintype "passive"))
      (node (ref "U1") (pin "19") (pinfunction "GPIO15/RTC_GPIO15/U0RTS/ADC2_CH4/XTAL_32K_P_19") (pintype "passive"))
    )
    (net (code "38") (name "/GPIO16") (class "Default")
      (node (ref "J1") (pin "19") (pinfunction "19_19") (pintype "passive"))
      (node (ref "U1") (pin "20") (pinfunction "GPIO16/RTC_GPIO16/U0CTS/ADC2_CH5/XTAL_32K_N_20") (pintype "passive"))
    )
    (net (code "39") (name "/GPIO17") (class "Default")
      (node (ref "J1") (pin "20") (pinfunction "20_20") (pintype "passive"))
      (node (ref "U1") (pin "21") (pinfunction "GPIO17/RTC_GPIO17/U1TXD/ADC2_CH6_21") (pintype "passive"))
    )
    (net (code "40") (name "/GPIO18") (class "Default")
      (node (ref "J1") (pin "21") (pinfunction "21_21") (pintype "passive"))
      (node (ref "U1") (pin "22") (pinfunction "GPIO18/RTC_GPIO18/U1RXD/ADC2_CH7/CLK_OUT3_22") (pintype "passive"))
    )
    (net (code "41") (name "/GPIO21") (class "Default")
      (node (ref "J2") (pin "19") (pinfunction "19_19") (pintype "passive"))
      (node (ref "U1") (pin "25") (pinfunction "GPIO21/RTC_GPIO21_25") (pintype "passive"))
    )
    (net (code "42") (name "/GPIO26") (class "Default")
      (node (ref "J2") (pin "18") (pinfunction "18_18") (pintype "passive"))
      (node (ref "U1") (pin "26") (pinfunction "GPIO26/SPICS1_26") (pintype "passive"))
    )
    (net (code "43") (name "/GPIO33") (class "Default")
      (node (ref "J2") (pin "17") (pinfunction "17_17") (pintype "passive"))
      (node (ref "U1") (pin "28") (pinfunction "GPIO33/SPIIO4/FSPIHD/SUBSPIHD_28") (pintype "passive"))
    )
    (net (code "44") (name "/GPIO34") (class "Default")
      (node (ref "J2") (pin "16") (pinfunction "16_16") (pintype "passive"))
      (node (ref "U1") (pin "29") (pinfunction "GPIO34/SPIIO5/FSPICS0/SUBSPICS0_29") (pintype "passive"))
    )
    (net (code "45") (name "/GPIO35") (class "Default")
      (node (ref "J2") (pin "15") (pinfunction "15_15") (pintype "passive"))
      (node (ref "U1") (pin "31") (pinfunction "GPIO35/SPIIO6/FSPID/SUBSPID_31") (pintype "passive"))
    )
    (net (code "46") (name "/GPIO36") (class "Default")
      (node (ref "J2") (pin "14") (pinfunction "14_14") (pintype "passive"))
      (node (ref "U1") (pin "32") (pinfunction "GPIO36/SPIIO7/FSPICLK/SUBSPICLK_32") (pintype "passive"))
    )
    (net (code "47") (name "/GPIO37") (class "Default")
      (node (ref "J2") (pin "13") (pinfunction "13_13") (pintype "passive"))
      (node (ref "U1") (pin "33") (pinfunction "GPIO37/SPIDQS/FSPIQ/SUBSPIQ_33") (pintype "passive"))
    )
    (net (code "48") (name "/GPIO38") (class "Default")
      (node (ref "J2") (pin "12") (pinfunction "12_12") (pintype "passive"))
      (node (ref "U1") (pin "34") (pinfunction "GPIO38/FSPIWP/SUBSPIWP_34") (pintype "passive"))
    )
    (net (code "49") (name "/GPIO39") (class "Default")
      (node (ref "J2") (pin "11") (pinfunction "11_11") (pintype "passive"))
      (node (ref "U1") (pin "35") (pinfunction "MTCK/GPIO39/CLK_OUT3/SUBSPICS1_35") (pintype "passive"))
    )
    (net (code "50") (name "/GPIO40") (class "Default")
      (node (ref "J2") (pin "10") (pinfunction "10_10") (pintype "passive"))
      (node (ref "U1") (pin "36") (pinfunction "MTDO/GPIO40/CLK_OUT2_36") (pintype "passive"))
    )
    (net (code "51") (name "/GPIO41") (class "Default")
      (node (ref "J2") (pin "9") (pinfunction "9_9") (pintype "passive"))
      (node (ref "U1") (pin "37") (pinfunction "MTDI/GPIO41/CLK_OUT1_37") (pintype "passive"))
    )
    (net (code "52") (name "/GPIO42") (class "Default")
      (node (ref "J2") (pin "8") (pinfunction "8_8") (pintype "passive"))
      (node (ref "U1") (pin "38") (pinfunction "MTMS/GPIO42_38") (pintype "passive"))
    )
    (net (code "53") (name "/GPIO45") (class "Default")
      (node (ref "J2") (pin "5") (pinfunction "5_5") (pintype "passive"))
      (node (ref "U1") (pin "41") (pinfunction "GPIO45_41") (pintype "passive"))
    )
    (net (code "54") (name "/GPIO46") (class "Default")
      (node (ref "J2") (pin "4") (pinfunction "4_4") (pintype "passive"))
      (node (ref "U1") (pin "44") (pinfunction "GPIO46_44") (pintype "passive"))
    )
    (net (code "55") (name "/GPIO47") (class "Default")
      (node (ref "J2") (pin "23") (pinfunction "23_23") (pintype "passive"))
      (node (ref "U1") (pin "27") (pinfunction "GPIO47/SPICLK_P_DIFF/SUBSPICLK_P_DIFF_27") (pintype "passive"))
    )
    (net (code "56") (name "/GPIO48") (class "Default")
      (node (ref "J2") (pin "22") (pinfunction "22_22") (pintype "passive"))
      (node (ref "U1") (pin "30") (pinfunction "GPIO48/SPICLK_N_DIFF/SUBSPICLK_N_DIFF_30") (pintype "passive"))
    )
    (net (code "57") (name "/RTS_FTDI") (class "Default")
      (node (ref "U2") (pin "19") (pinfunction "~{RTS}_19") (pintype "passive"))
    )
    (net (code "58") (name "/RXD_FTDI") (class "Default")
      (node (ref "R19") (pin "2") (pinfunction "2_2") (pintype "passive"))
      (node (ref "U2") (pin "1") (pinfunction "RXD_1") (pintype "passive"))
    )
    (net (code "59") (name "/TXD_FTDI") (class "Default")
      (node (ref "R20") (pin "2") (pinfunction "2_2") (pintype "passive"))
      (node (ref "U2") (pin "17") (pinfunction "TXD_17") (pintype "passive"))
    )
    (net (code "60") (name "/U0RXD") (class "Default")
      (node (ref "J2") (pin "6") (pinfunction "6_6") (pintype "passive"))
      (node (ref "R20") (pin "1") (pinfunction "1_1") (pintype "passive"))
      (node (ref "U1") (pin "40") (pinfunction "U0RXD/GPIO44/CLK_OUT2_40") (pintype "passive"))
    )
    (net (code "61") (name "/U0TXD") (class "Default")
      (node (ref "J2") (pin "7") (pinfunction "7_7") (pintype "passive"))
      (node (ref "R19") (pin "1") (pinfunction "1_1") (pintype "passive"))
      (node (ref "U1") (pin "39") (pinfunction "U0TXD/GPIO43/CLK_OUT1_39") (pintype "passive"))
    )
    (net (code "62") (name "/VBUS_SENSE") (class "Default")
      (node (ref "R10") (pin "1") (pinfunction "1_1") (pintype "passive"))
      (node (ref "R13") (pin "1") (pinfunction "1_1") (pintype "passive"))
      (node (ref "U2") (pin "16") (pinfunction "CBUS3_16") (pintype "passive"))
    )
    (net (code "63") (name "GND") (class "Default")
      (node (ref "C1") (pin "1") (pinfunction "1_1") (pintype "passive"))
      (node (ref "C14") (pin "1") (pinfunction "1_1") (pintype "passive"))
      (node (ref "C15") (pin "1") (pinfunction "1_1") (pintype "passive"))
      (node (ref "C16") (pin "1") (pinfunction "1_1") (pintype "passive"))
      (node (ref "C17") (pin "1") (pinfunction "1_1") (pintype "passive"))
      (node (ref "C2") (pin "1") (pinfunction "1_1") (pintype "passive"))
      (node (ref "C3") (pin "1") (pinfunction "1_1") (pintype "passive"))
      (node (ref "C4") (pin "1") (pinfunction "1_1") (pintype "passive"))
      (node (ref "C5") (pin "1") (pinfunction "1_1") (pintype "passive"))
      (node (ref "C6") (pin "1") (pinfunction "1_1") (pintype "passive"))
      (node (ref "C7") (pin "1") (pinfunction "1_1") (pintype "passive"))
      (node (ref "C8") (pin "1") (pinfunction "1_1") (pintype "passive"))
      (node (ref "C9") (pin "1") (pinfunction "1_1") (pintype "passive"))
      (node (ref "D1") (pin "1") (pinfunction "1_1") (pintype "passive"))
      (node (ref "D3") (pin "1") (pinfunction "1_1") (pintype "passive"))
      (node (ref "D4") (pin "1") (pinfunction "1_1") (pintype "passive"))
      (node (ref "D5") (pin "1") (pinfunction "1_1") (pintype "passive"))
      (node (ref "J1") (pin "1") (pinfunction "1_1") (pintype "passive"))
      (node (ref "J1") (pin "23") (pinfunction "23_23") (pintype "passive"))
      (node (ref "J2") (pin "2") (pinfunction "2_2") (pintype "passive"))
      (node (ref "J2") (pin "24") (pinfunction "24_24") (pintype "passive"))
      (node (ref "J3") (pin "A1B12") (pinfunction "GND_A1B12_A1B12") (pintype "passive"))
      (node (ref "J3") (pin "B1A12") (pinfunction "GND_B1A12_B1A12") (pintype "passive"))
      (node (ref "J3") (pin "S1") (pinfunction "SHIELD_1_S1") (pintype "passive"))
      (node (ref "J3") (pin "S2") (pinfunction "SHIELD_2_S2") (pintype "passive"))
      (node (ref "J3") (pin "S3") (pinfunction "SHIELD_3_S3") (pintype "passive"))
      (node (ref "J3") (pin "S4") (pinfunction "SHIELD_4_S4") (pintype "passive"))
      (node (ref "R11") (pin "1") (pinfunction "1_1") (pintype "passive"))
      (node (ref "R12") (pin "1") (pinfunction "1_1") (pintype "passive"))
      (node (ref "R13") (pin "2") (pinfunction "2_2") (pintype "passive"))
      (node (ref "R9") (pin "2") (pinfunction "2_2") (pintype "passive"))
      (node (ref "SW1") (pin "3") (pinfunction "3_3") (pintype "passive"))
      (node (ref "SW1") (pin "4") (pinfunction "4_4") (pintype "passive"))
      (node (ref "SW2") (pin "3") (pinfunction "3_3") (pintype "passive"))
      (node (ref "SW2") (pin "4") (pinfunction "4_4") (pintype "passive"))
      (node (ref "U1") (pin "1") (pinfunction "GND_01_1") (pintype "passive"))
      (node (ref "U1") (pin "2") (pinfunction "GND_02_2") (pintype "passive"))
      (node (ref "U1") (pin "42") (pinfunction "GND_42") (pintype "passive"))
      (node (ref "U1") (pin "43") (pinfunction "GND_43") (pintype "passive"))
      (node (ref "U1") (pin "46") (pinfunction "GND_46_46") (pintype "passive"))
      (node (ref "U1") (pin "47") (pinfunction "GND_47_47") (pintype "passive"))
      (node (ref "U1") (pin "48") (pinfunction "GND_48_48") (pintype "passive"))
      (node (ref "U1") (pin "49") (pinfunction "GND_49_49") (pintype "passive"))
      (node (ref "U1") (pin "50") (pinfunction "GND_50_50") (pintype "passive"))
      (node (ref "U1") (pin "51") (pinfunction "GND_51_51") (pintype "passive"))
      (node (ref "U1") (pin "52") (pinfunction "GND_52_52") (pintype "passive"))
      (node (ref "U1") (pin "53") (pinfunction "GND_53_53") (pintype "passive"))
      (node (ref "U1") (pin "54") (pinfunction "GND_54_54") (pintype "passive"))
      (node (ref "U1") (pin "55") (pinfunction "GND_55_55") (pintype "passive"))
      (node (ref "U1") (pin "56") (pinfunction "GND_56_56") (pintype "passive"))
      (node (ref "U1") (pin "57") (pinfunction "GND_57_57") (pintype "passive"))
      (node (ref "U1") (pin "58") (pinfunction "GND_58_58") (pintype "passive"))
      (node (ref "U1") (pin "59") (pinfunction "GND_59_59") (pintype "passive"))
      (node (ref "U1") (pin "60") (pinfunction "GND_60_60") (pintype "passive"))
      (node (ref "U1") (pin "61") (pinfunction "GND_61_61") (pintype "passive"))
      (node (ref "U1") (pin "62") (pinfunction "GND_62_62") (pintype "passive"))
      (node (ref "U1") (pin "63") (pinfunction "GND_63_63") (pintype "passive"))
      (node (ref "U1") (pin "64") (pinfunction "GND_64_64") (pintype "passive"))
      (node (ref "U1") (pin "65") (pinfunction "GND_65_65") (pintype "passive"))
      (node (ref "U1") (pin "66") (pinfunction "GND_66_66") (pintype "passive"))
      (node (ref "U1") (pin "67") (pinfunction "GND_67_67") (pintype "passive"))
      (node (ref "U1") (pin "68") (pinfunction "GND_68_68") (pintype "passive"))
      (node (ref "U1") (pin "69") (pinfunction "GND_69_69") (pintype "passive"))
      (node (ref "U1") (pin "70") (pinfunction "GND_70_70") (pintype "passive"))
      (node (ref "U1") (pin "71") (pinfunction "GND_71_71") (pintype "passive"))
      (node (ref "U1") (pin "72") (pinfunction "GND_72_72") (pintype "passive"))
      (node (ref "U1") (pin "73") (pinfunction "GND_73_73") (pintype "passive"))
      (node (ref "U2") (pin "13") (pinfunction "GND_13") (pintype "passive"))
      (node (ref "U2") (pin "21") (pinfunction "GND_21") (pintype "passive"))
      (node (ref "U2") (pin "3") (pinfunction "GND_3") (pintype "passive"))
    )
    (net (code "64") (name "Net-(D1-Pad2)") (class "Default")
      (node (ref "D1") (pin "2") (pinfunction "2_2") (pintype "passive"))
      (node (ref "R3") (pin "1") (pinfunction "1_1") (pintype "passive"))
    )
    (net (code "65") (name "Net-(D2-Pad2)") (class "Default")
      (node (ref "D2") (pin "2") (pinfunction "2_2") (pintype "passive"))
      (node (ref "R4") (pin "1") (pinfunction "1_1") (pintype "passive"))
    )
    (net (code "66") (name "Net-(J3-CC1)") (class "Default")
      (node (ref "J3") (pin "A5") (pinfunction "CC1_A5") (pintype "passive"))
      (node (ref "R12") (pin "2") (pinfunction "2_2") (pintype "passive"))
    )
    (net (code "67") (name "Net-(J3-CC2)") (class "Default")
      (node (ref "J3") (pin "B5") (pinfunction "CC2_B5") (pintype "passive"))
      (node (ref "R11") (pin "2") (pinfunction "2_2") (pintype "passive"))
    )
    (net (code "68") (name "Net-(U2-CBUS0)") (class "Default")
      (node (ref "R9") (pin "1") (pinfunction "1_1") (pintype "passive"))
      (node (ref "U2") (pin "15") (pinfunction "CBUS0_15") (pintype "passive"))
    )
    (net (code "69") (name "unconnected-(J1-Pad24)") (class "Default")
      (node (ref "J1") (pin "24") (pinfunction "24_24") (pintype "passive+no_connect"))
    )
    (net (code "70") (name "unconnected-(J3-SBU1-PadA8)") (class "Default")
      (node (ref "J3") (pin "A8") (pinfunction "SBU1_A8") (pintype "passive+no_connect"))
    )
    (net (code "71") (name "unconnected-(J3-SBU2-PadB8)") (class "Default")
      (node (ref "J3") (pin "B8") (pinfunction "SBU2_B8") (pintype "passive+no_connect"))
    )
    (net (code "72") (name "unconnected-(U2-CBUS1-Pad14)") (class "Default")
      (node (ref "U2") (pin "14") (pinfunction "CBUS1_14") (pintype "passive+no_connect"))
    )
    (net (code "73") (name "unconnected-(U2-CBUS2-Pad7)") (class "Default")
      (node (ref "U2") (pin "7") (pinfunction "CBUS2_7") (pintype "passive+no_connect"))
    )
    (net (code "74") (name "unconnected-(U2-~{CTS}-Pad6)") (class "Default")
      (node (ref "U2") (pin "6") (pinfunction "~{CTS}_6") (pintype "passive+no_connect"))
    )
    (net (code "75") (name "unconnected-(U2-~{DCD}-Pad5)") (class "Default")
      (node (ref "U2") (pin "5") (pinfunction "~{DCD}_5") (pintype "passive+no_connect"))
    )
    (net (code "76") (name "unconnected-(U2-~{DSR}-Pad4)") (class "Default")
      (node (ref "U2") (pin "4") (pinfunction "~{DSR}_4") (pintype "passive+no_connect"))
    )
    (net (code "77") (name "unconnected-(U2-~{RI}-Pad2)") (class "Default")
      (node (ref "U2") (pin "2") (pinfunction "~{RI}_2") (pintype "passive+no_connect"))
    )
  )
)
